# Sheet1.net
KiCad netlist of a schematic drawn in Altium Designer
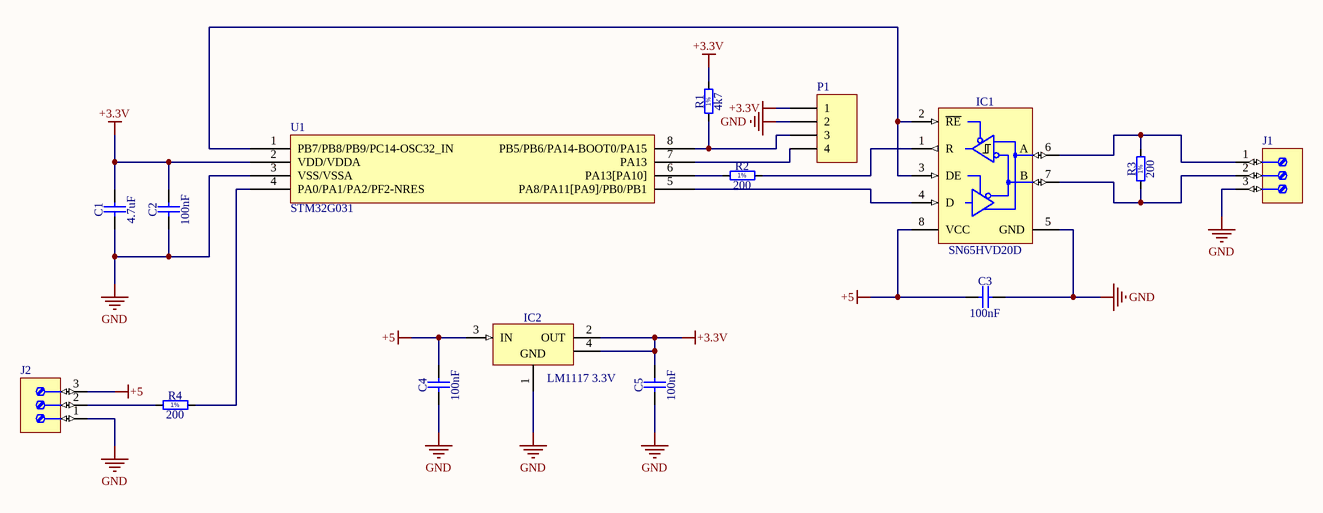
[diagram p0: Sheet1.SchDoc]

(export (version "E")
  (design (tool "Eeschema 10.0.6"))
  (components
    (comp (ref "C1")
      (value "4.7uF")
      (footprint "CAPC2012X135N")
      (description "Non-polarised capacitor")
      (fields
        (field (name "PART NUMBER") "CC0805_4.7UF_16V_10%_X7R")
        (field (name "VOLTAGE") "16V")
        (field (name "AUTHOR") "CERN DEM JLC")
      )
      (libsource (lib "Capacitors") (part "Capacitor - non polarized"))
    )
    (comp (ref "C2")
      (value "100nF")
      (footprint "CAPC2012X135N")
      (description "Non-polarised capacitor")
      (fields
        (field (name "PART NUMBER") "CC0805_100NF_50V_10%_X7R")
        (field (name "VOLTAGE") "50V")
        (field (name "AUTHOR") "CERN DEM JLC")
      )
      (libsource (lib "Capacitors") (part "Capacitor - non polarized"))
    )
    (comp (ref "C3")
      (value "100nF")
      (footprint "CAPC2012X135N")
      (description "Non-polarised capacitor")
      (fields
        (field (name "PART NUMBER") "CC0805_100NF_50V_10%_X7R")
        (field (name "VOLTAGE") "50V")
        (field (name "AUTHOR") "CERN DEM JLC")
      )
      (libsource (lib "Capacitors") (part "Capacitor - non polarized"))
    )
    (comp (ref "C4")
      (value "100nF")
      (footprint "CAPC2012X135N")
      (description "Non-polarised capacitor")
      (fields
        (field (name "PART NUMBER") "CC0805_100NF_50V_10%_X7R")
        (field (name "VOLTAGE") "50V")
        (field (name "AUTHOR") "CERN DEM JLC")
      )
      (libsource (lib "Capacitors") (part "Capacitor - non polarized"))
    )
    (comp (ref "C5")
      (value "100nF")
      (footprint "CAPC2012X135N")
      (description "Non-polarised capacitor")
      (fields
        (field (name "PART NUMBER") "CC0805_100NF_50V_10%_X7R")
        (field (name "VOLTAGE") "50V")
        (field (name "AUTHOR") "CERN DEM JLC")
      )
      (libsource (lib "Capacitors") (part "Capacitor - non polarized"))
    )
    (comp (ref "IC1")
      (value "SN65HVD20D")
      (footprint "SOIC127P600X175-8N")
      (description "Extended Common-Mode RS-485 Transceiver")
      (fields (field (name "MANUFACTURER") "TEXAS INSTRUMENTS") (field (name "AUTHOR") "CERN DEM JLC"))
      (libsource (lib "ICs And Semiconductors") (part "SN65HVD20"))
    )
    (comp (ref "IC2")
      (value "LM1117 3.3V")
      (footprint "SOT230P700X180-4N")
      (description "3-Terminal Regulator 1=GND 2=OUT 3=IN 4=OUT")
      (fields
        (field (name "PART NUMBER") "LM1117MP-1.8/NOPB")
        (field (name "MANUFACTURER") "TEXAS INSTRUMENTS")
        (field (name "AUTHOR") "CERN DEM JLC")
      )
      (libsource (lib "ICs And Semiconductors") (part "REG3+1 1GND-2OUT-3IN+4OUT"))
    )
    (comp (ref "J1")
      (value "~")
      (footprint "PHOENIX_1707917")
      (description "Terminal Block, 3 Positions, Screw Connection")
      (fields
        (field (name "PART NUMBER") "PHOENIX_1707917")
        (field (name "MANUFACTURER") "PHOENIX CONTACT")
        (field (name "AUTHOR") "CERN DEM JLC")
      )
      (libsource (lib "Connectors") (part "Terminal Block_3 Positions_Screw Connection"))
    )
    (comp (ref "J2")
      (value "~")
      (footprint "PHOENIX_1707917")
      (description "Terminal Block, 3 Positions, Screw Connection")
      (fields
        (field (name "PART NUMBER") "PHOENIX_1707917")
        (field (name "MANUFACTURER") "PHOENIX CONTACT")
        (field (name "AUTHOR") "CERN DEM JLC")
      )
      (libsource (lib "") (part "Terminal Block_3 Positions_Screw Connection_1"))
    )
    (comp (ref "P1")
      (value "Header 4")
      (footprint "HDR1X4")
      (description "Header, 4-Pin")
      (fields (field (name "PUBLISHER") "Altium Limited"))
      (libsource (lib "Miscellaneous Connectors") (part "Header 4"))
    )
    (comp (ref "R1")
      (value "4k7")
      (footprint "RESC2012X60N")
      (description "Resistor - 1%")
      (fields
        (field (name "PART NUMBER") "R0805_4K7_1%_0.125W_100PPM")
        (field (name "POWER") "0.125W")
        (field (name "AUTHOR") "CERN DEM JLC")
      )
      (libsource (lib "Resistors") (part "Resistor - 1%"))
    )
    (comp (ref "R2")
      (value "200")
      (footprint "RESC2012X60N")
      (description "Resistor - 1%")
      (fields
        (field (name "PART NUMBER") "R0805_200R_1%_0.125W_100PPM")
        (field (name "POWER") "0.125W")
        (field (name "AUTHOR") "CERN DEM JLC")
      )
      (libsource (lib "Resistors") (part "Resistor - 1%"))
    )
    (comp (ref "R3")
      (value "200")
      (footprint "RESC2012X60N")
      (description "Resistor - 1%")
      (fields
        (field (name "PART NUMBER") "R0805_200R_1%_0.125W_100PPM")
        (field (name "POWER") "0.125W")
        (field (name "AUTHOR") "CERN DEM JLC")
      )
      (libsource (lib "Resistors") (part "Resistor - 1%"))
    )
    (comp (ref "R4")
      (value "200")
      (footprint "RESC2012X60N")
      (description "Resistor - 1%")
      (fields
        (field (name "PART NUMBER") "R0805_200R_1%_0.125W_100PPM")
        (field (name "POWER") "0.125W")
        (field (name "AUTHOR") "CERN DEM JLC")
      )
      (libsource (lib "Resistors") (part "Resistor - 1%"))
    )
    (comp (ref "U1")
      (value "STM32G031")
      (footprint "PCB - LEADED - SOIC - ST SOIC-8N:ST SOIC-8N")
      (libsource (lib "stm32g031") (part "STM32G031"))
    )
  )
  (nets
    (net (code "1") (name "+3.3V") (class "Default")
      (node (ref "C1") (pin "2") (pinfunction "2_2") (pintype "passive"))
      (node (ref "C2") (pin "2") (pinfunction "2_2") (pintype "passive"))
      (node (ref "C5") (pin "2") (pinfunction "2_2") (pintype "passive"))
      (node (ref "IC2") (pin "2") (pinfunction "OUT_2") (pintype "power_in"))
      (node (ref "IC2") (pin "4") (pinfunction "OUT_4") (pintype "power_in"))
      (node (ref "P1") (pin "1") (pinfunction "1_1") (pintype "passive"))
      (node (ref "R1") (pin "2") (pinfunction "2_2") (pintype "passive"))
      (node (ref "U1") (pin "2") (pinfunction "VDD/VDDA_2") (pintype "passive"))
    )
    (net (code "2") (name "+5") (class "Default")
      (node (ref "C3") (pin "1") (pinfunction "1_1") (pintype "passive"))
      (node (ref "C4") (pin "2") (pinfunction "2_2") (pintype "passive"))
      (node (ref "IC1") (pin "8") (pinfunction "VCC_8") (pintype "power_in"))
      (node (ref "IC2") (pin "3") (pinfunction "IN_3") (pintype "input"))
      (node (ref "J2") (pin "3") (pinfunction "3_3") (pintype "bidirectional"))
    )
    (net (code "3") (name "GND") (class "Default")
      (node (ref "C1") (pin "1") (pinfunction "1_1") (pintype "passive"))
      (node (ref "C2") (pin "1") (pinfunction "1_1") (pintype "passive"))
      (node (ref "C3") (pin "2") (pinfunction "2_2") (pintype "passive"))
      (node (ref "C4") (pin "1") (pinfunction "1_1") (pintype "passive"))
      (node (ref "C5") (pin "1") (pinfunction "1_1") (pintype "passive"))
      (node (ref "IC1") (pin "5") (pinfunction "GND_5") (pintype "power_in"))
      (node (ref "IC2") (pin "1") (pinfunction "GND_1") (pintype "power_in"))
      (node (ref "J1") (pin "3") (pinfunction "3_3") (pintype "bidirectional"))
      (node (ref "J2") (pin "1") (pinfunction "1_1") (pintype "bidirectional"))
      (node (ref "P1") (pin "2") (pinfunction "2_2") (pintype "passive"))
      (node (ref "U1") (pin "3") (pinfunction "VSS/VSSA_3") (pintype "passive"))
    )
    (net (code "4") (name "Net-(IC1-A)") (class "Default")
      (node (ref "IC1") (pin "6") (pinfunction "A_6") (pintype "bidirectional"))
      (node (ref "J1") (pin "1") (pinfunction "1_1") (pintype "bidirectional"))
      (node (ref "R3") (pin "2") (pinfunction "2_2") (pintype "passive"))
    )
    (net (code "5") (name "Net-(IC1-B)") (class "Default")
      (node (ref "IC1") (pin "7") (pinfunction "B_7") (pintype "bidirectional"))
      (node (ref "J1") (pin "2") (pinfunction "2_2") (pintype "bidirectional"))
      (node (ref "R3") (pin "1") (pinfunction "1_1") (pintype "passive"))
    )
    (net (code "6") (name "Net-(IC1-D)") (class "Default")
      (node (ref "IC1") (pin "4") (pinfunction "D_4") (pintype "input"))
      (node (ref "U1") (pin "5") (pinfunction "PA8/PA11[PA9]/PB0/PB1_5") (pintype "passive"))
    )
    (net (code "7") (name "Net-(IC1-DE)") (class "Default")
      (node (ref "IC1") (pin "2") (pinfunction "~{RE}_2") (pintype "input"))
      (node (ref "IC1") (pin "3") (pinfunction "DE_3") (pintype "input"))
      (node (ref "U1") (pin "1") (pinfunction "PB7/PB8/PB9/PC14-OSC32_IN_1") (pintype "passive"))
    )
    (net (code "8") (name "Net-(IC1-R)") (class "Default")
      (node (ref "IC1") (pin "1") (pinfunction "R_1") (pintype "output"))
      (node (ref "R2") (pin "2") (pinfunction "2_2") (pintype "passive"))
    )
    (net (code "9") (name "Net-(J2-Pad2)") (class "Default")
      (node (ref "J2") (pin "2") (pinfunction "2_2") (pintype "bidirectional"))
      (node (ref "R4") (pin "1") (pinfunction "1_1") (pintype "passive"))
    )
    (net (code "10") (name "Net-(U1-PA0{slash}PA1{slash}PA2{slash}PF2-NRES)") (class "Default")
      (node (ref "R4") (pin "2") (pinfunction "2_2") (pintype "passive"))
      (node (ref "U1") (pin "4") (pinfunction "PA0/PA1/PA2/PF2-NRES_4") (pintype "passive"))
    )
    (net (code "11") (name "Net-(U1-PA13)") (class "Default")
      (node (ref "P1") (pin "4") (pinfunction "4_4") (pintype "passive"))
      (node (ref "U1") (pin "7") (pinfunction "PA13_7") (pintype "passive"))
    )
    (net (code "12") (name "Net-(U1-PA13[PA10])") (class "Default")
      (node (ref "R2") (pin "1") (pinfunction "1_1") (pintype "passive"))
      (node (ref "U1") (pin "6") (pinfunction "PA13[PA10]_6") (pintype "passive"))
    )
    (net (code "13") (name "Net-(U1-PB5{slash}PB6{slash}PA14-BOOT0{slash}PA15)") (class "Default")
      (node (ref "P1") (pin "3") (pinfunction "3_3") (pintype "passive"))
      (node (ref "R1") (pin "1") (pinfunction "1_1") (pintype "passive"))
      (node (ref "U1") (pin "8") (pinfunction "PB5/PB6/PA14-BOOT0/PA15_8") (pintype "passive"))
    )
  )
)
